# schematic-3_3V.net
KiCad netlist of a schematic drawn in EAGLE
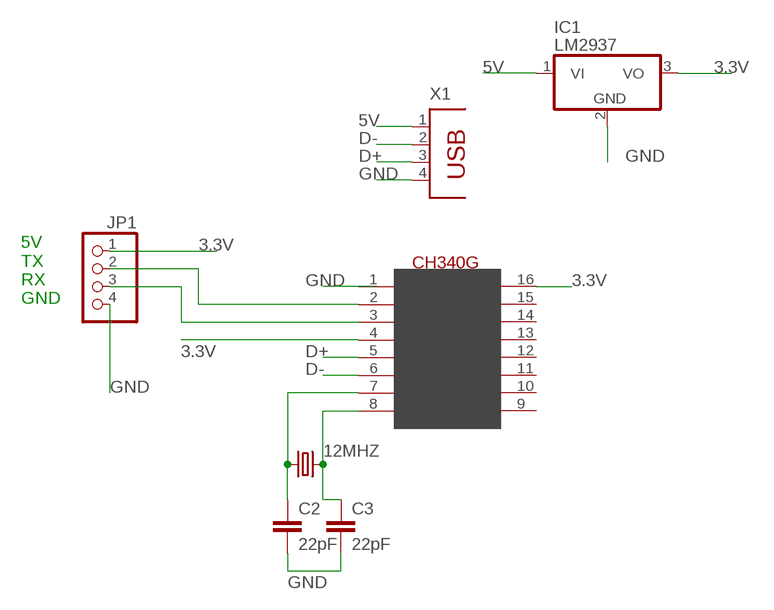
[diagram p0: schematic, sheet 1]

(export (version "E")
  (design (tool "Eeschema 10.0.6"))
  (components
    (comp (ref "12MHZ")
      (value "CRYSTALHC18U-V")
      (footprint "eagle-import:HC18U-V")
      (libsource (lib "eagle-import") (part "CRYSTALHC18U-V"))
    )
    (comp (ref "C2")
      (value "22pF")
      (footprint "eagle-import:C2.5-2")
      (libsource (lib "eagle-import") (part "C2.5/2"))
    )
    (comp (ref "C3")
      (value "22pF")
      (footprint "eagle-import:C2.5-2")
      (libsource (lib "eagle-import") (part "C2.5/2"))
    )
    (comp (ref "IC1")
      (value "LM2937")
      (footprint "eagle-import:TO263-3")
      (libsource (lib "eagle-import") (part "LM2937"))
    )
    (comp (ref "JP1")
      (value "PINHD-1X4")
      (footprint "eagle-import:1X04")
      (libsource (lib "eagle-import") (part "PINHD-1X4"))
    )
    (comp (ref "U$1")
      (value "CH340G")
      (footprint "eagle-import:SOIC16")
      (libsource (lib "eagle-import") (part "CH340G"))
    )
    (comp (ref "X1")
      (value "PN61729")
      (footprint "eagle-import:PN61729")
      (libsource (lib "eagle-import") (part "PN61729"))
    )
  )
  (nets
    (net (code "1") (name "/3.3V") (class "Default")
      (node (ref "IC1") (pin "3") (pinfunction "VO_3") (pintype "passive"))
      (node (ref "JP1") (pin "1") (pinfunction "1_1") (pintype "passive"))
      (node (ref "U$1") (pin "16") (pinfunction "VCC_16") (pintype "bidirectional"))
      (node (ref "U$1") (pin "4") (pinfunction "V3_4") (pintype "bidirectional"))
    )
    (net (code "2") (name "/5V") (class "Default")
      (node (ref "IC1") (pin "1") (pinfunction "VI_1") (pintype "input"))
      (node (ref "X1") (pin "1") (pinfunction "1_1") (pintype "passive"))
    )
    (net (code "3") (name "/D+") (class "Default")
      (node (ref "U$1") (pin "5") (pinfunction "D+_5") (pintype "bidirectional"))
      (node (ref "X1") (pin "3") (pinfunction "3_3") (pintype "passive"))
    )
    (net (code "4") (name "/D-") (class "Default")
      (node (ref "U$1") (pin "6") (pinfunction "D-_6") (pintype "bidirectional"))
      (node (ref "X1") (pin "2") (pinfunction "2_2") (pintype "passive"))
    )
    (net (code "5") (name "/GND") (class "Default")
      (node (ref "C2") (pin "2") (pinfunction "2_2") (pintype "passive"))
      (node (ref "C3") (pin "2") (pinfunction "2_2") (pintype "passive"))
      (node (ref "IC1") (pin "2") (pinfunction "GND_2") (pintype "passive"))
      (node (ref "JP1") (pin "4") (pinfunction "4_4") (pintype "passive"))
      (node (ref "X1") (pin "4") (pinfunction "4_4") (pintype "passive"))
    )
    (net (code "6") (name "Net-(U$1-RX)") (class "Default")
      (node (ref "JP1") (pin "3") (pinfunction "3_3") (pintype "passive"))
      (node (ref "U$1") (pin "3") (pinfunction "RX_3") (pintype "bidirectional"))
    )
    (net (code "7") (name "Net-(U$1-TX)") (class "Default")
      (node (ref "JP1") (pin "2") (pinfunction "2_2") (pintype "passive"))
      (node (ref "U$1") (pin "2") (pinfunction "TX_2") (pintype "bidirectional"))
    )
    (net (code "8") (name "Net-(U$1-XI)") (class "Default")
      (node (ref "12MHZ") (pin "1") (pinfunction "1_1") (pintype "passive"))
      (node (ref "C2") (pin "1") (pinfunction "1_1") (pintype "passive"))
      (node (ref "U$1") (pin "7") (pinfunction "XI_7") (pintype "bidirectional"))
    )
    (net (code "9") (name "Net-(U$1-XO)") (class "Default")
      (node (ref "12MHZ") (pin "2") (pinfunction "2_2") (pintype "passive"))
      (node (ref "C3") (pin "1") (pinfunction "1_1") (pintype "passive"))
      (node (ref "U$1") (pin "8") (pinfunction "XO_8") (pintype "bidirectional"))
    )
    (net (code "10") (name "unconnected-(U$1-CTS-Pad9)") (class "Default")
      (node (ref "U$1") (pin "9") (pinfunction "CTS_9") (pintype "bidirectional"))
    )
    (net (code "11") (name "unconnected-(U$1-DCD-Pad12)") (class "Default")
      (node (ref "U$1") (pin "12") (pinfunction "DCD_12") (pintype "bidirectional"))
    )
    (net (code "12") (name "unconnected-(U$1-DSR-Pad10)") (class "Default")
      (node (ref "U$1") (pin "10") (pinfunction "DSR_10") (pintype "bidirectional"))
    )
    (net (code "13") (name "unconnected-(U$1-DTR-Pad13)") (class "Default")
      (node (ref "U$1") (pin "13") (pinfunction "DTR_13") (pintype "bidirectional"))
    )
    (net (code "14") (name "unconnected-(U$1-GND-Pad1)") (class "Default")
      (node (ref "U$1") (pin "1") (pinfunction "GND_1") (pintype "bidirectional"))
    )
    (net (code "15") (name "unconnected-(U$1-RI-Pad11)") (class "Default")
      (node (ref "U$1") (pin "11") (pinfunction "RI_11") (pintype "bidirectional"))
    )
    (net (code "16") (name "unconnected-(U$1-RS232-Pad15)") (class "Default")
      (node (ref "U$1") (pin "15") (pinfunction "RS232_15") (pintype "bidirectional"))
    )
    (net (code "17") (name "unconnected-(U$1-RTS-Pad14)") (class "Default")
      (node (ref "U$1") (pin "14") (pinfunction "RTS_14") (pintype "bidirectional"))
    )
  )
)
